# Power_PMIC.net
KiCad netlist of a schematic drawn in Altium Designer
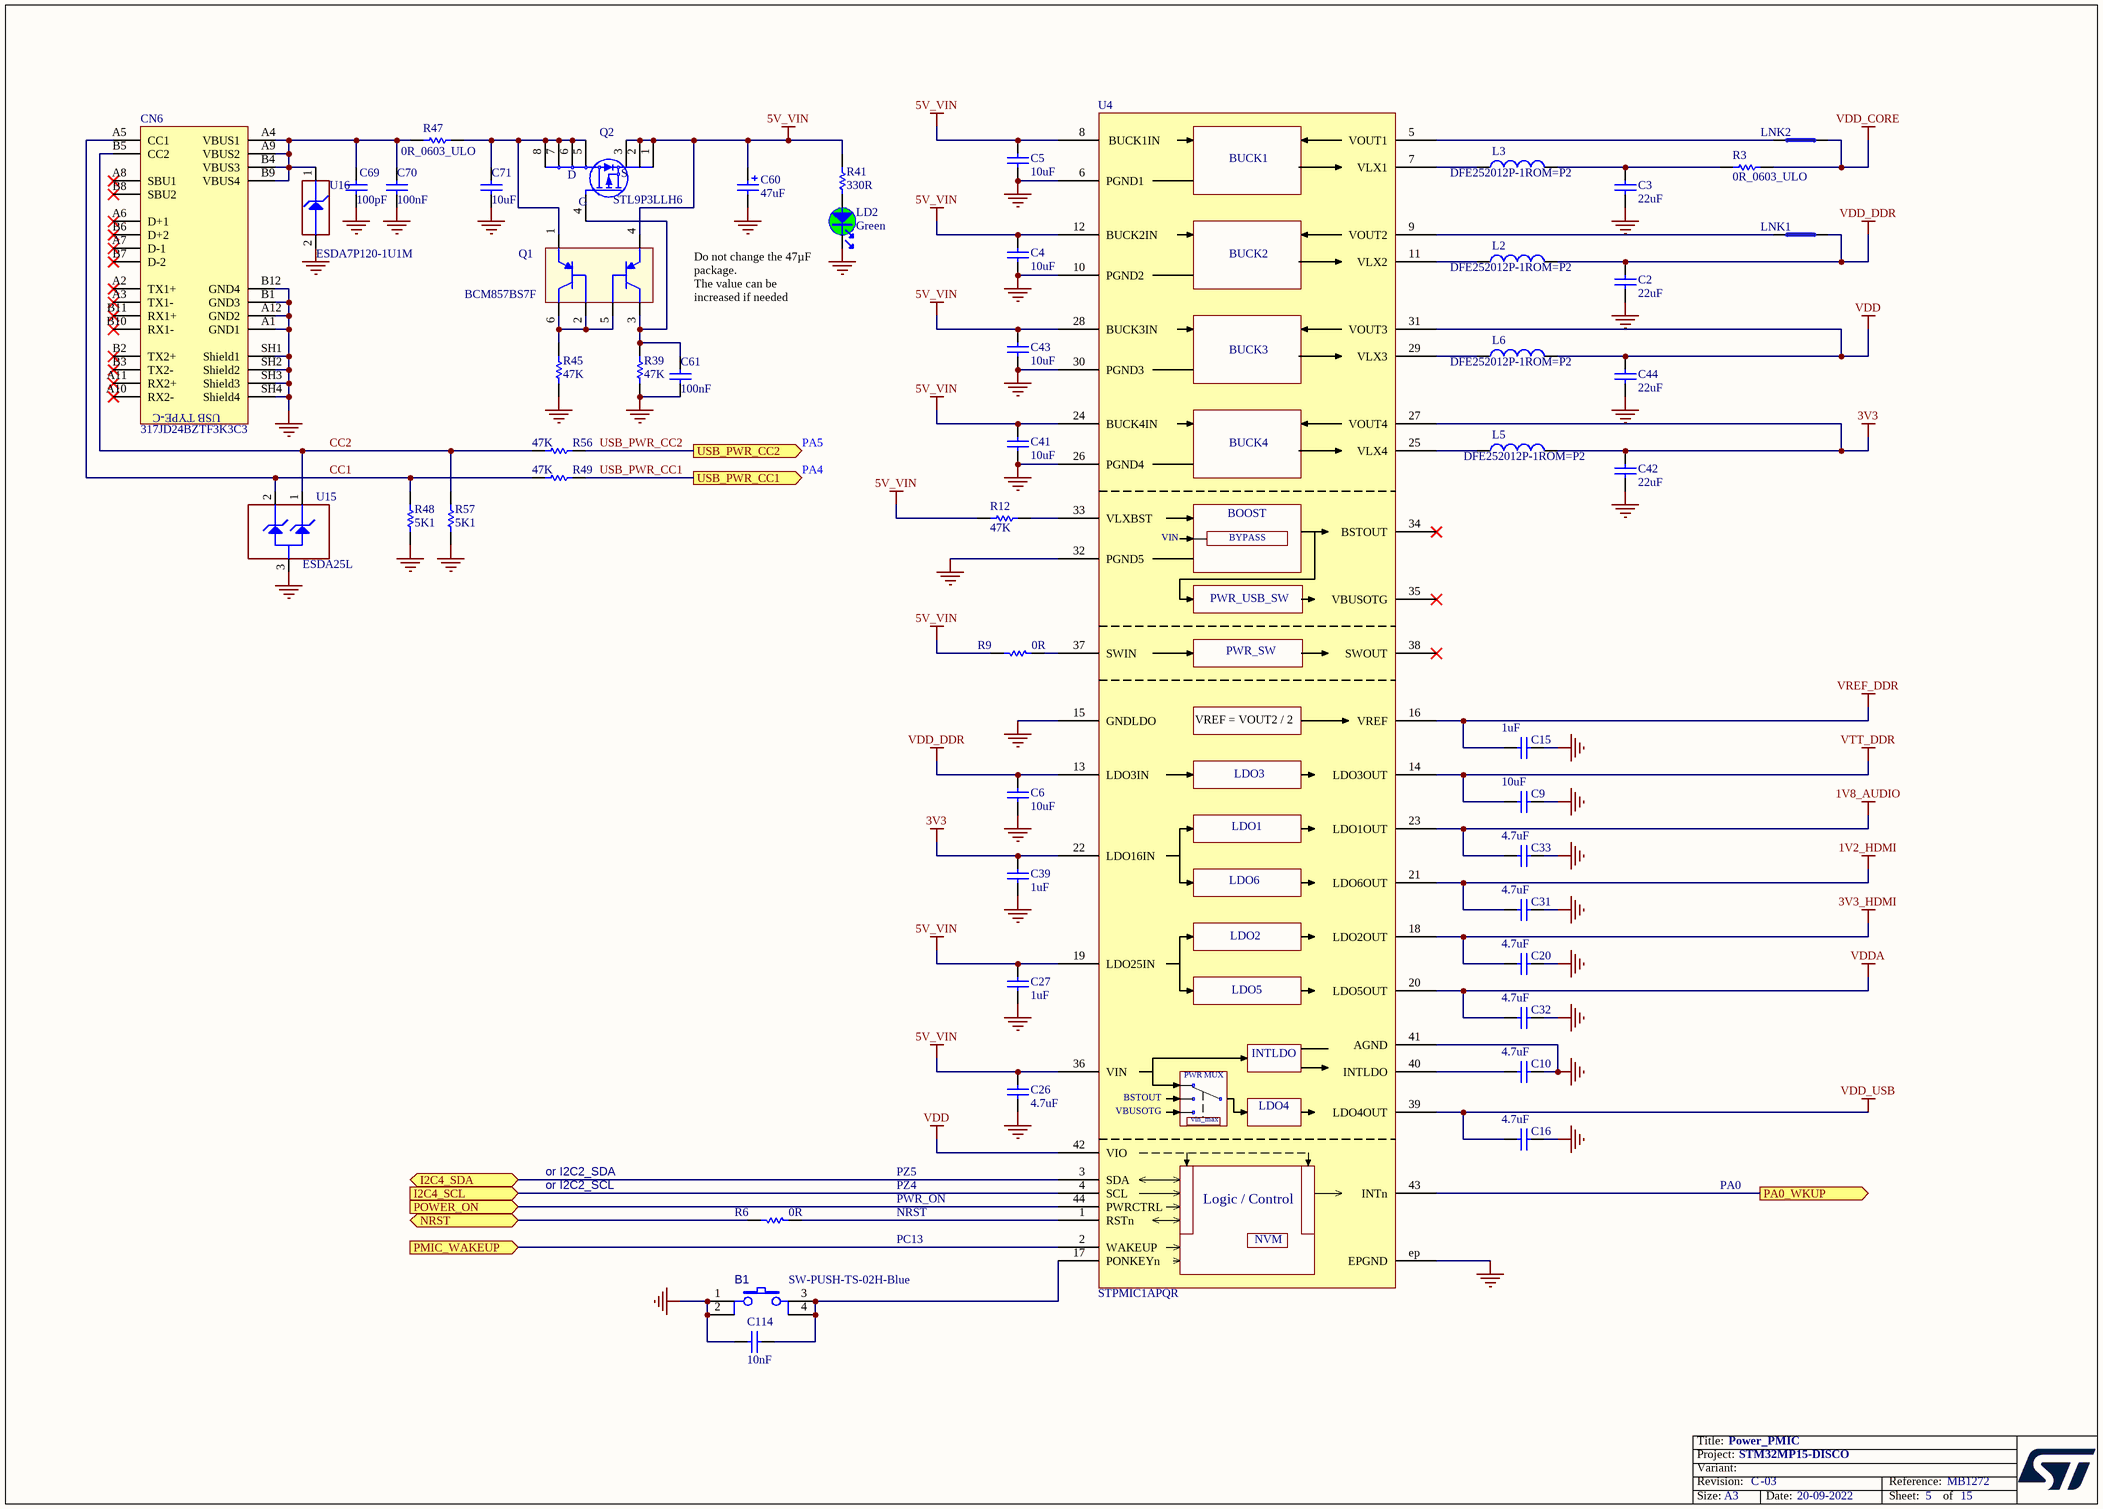
[diagram p0: Power_PMIC.SchDoc]

(export (version "E")
  (design (tool "Eeschema 10.0.6"))
  (components
    (comp (ref "B1")
      (value "SW-PUSH-TS-02H-Blue")
      (footprint "SWI_JIUBABA_C-TS-02H-2-5-B-V-T_R_BLUE")
      (description "Switch HW SMD blue")
      (fields
        (field (name "INTERNAL_PART_NUMBER") "MCD-00172")
        (field (name "MANUFACTURER_PART_NUMBER") "C-TS-02H-2.5-B-V-T/R BLUE")
        (field (name "PROVIDED_BY") "SUBCO")
      )
      (libsource (lib "MCD_PARTS_database") (part "SW-PUSH-TS-02H-Blue"))
    )
    (comp (ref "C2")
      (value "22uF")
      (footprint "C0603")
      (description "Capacitor, MLCC, 22uF, 6V3, X5R, 20%, 0603, T=0,8mm")
      (fields
        (field (name "INTERNAL_PART_NUMBER") "MCD-00100")
        (field (name "MANUFACTURER_PART_NUMBER") "GRM188R60J226MEA0J")
        (field (name "PROVIDED_BY") "SUBCO")
      )
      (libsource (lib "MCD_PARTS_database") (part "Capacitor"))
    )
    (comp (ref "C3")
      (value "22uF")
      (footprint "C0603")
      (description "Capacitor, MLCC, 22uF, 6V3, X5R, 20%, 0603, T=0,8mm")
      (fields
        (field (name "INTERNAL_PART_NUMBER") "MCD-00100")
        (field (name "MANUFACTURER_PART_NUMBER") "GRM188R60J226MEA0J")
        (field (name "PROVIDED_BY") "SUBCO")
      )
      (libsource (lib "MCD_PARTS_database") (part "Capacitor"))
    )
    (comp (ref "C4")
      (value "10uF")
      (footprint "C0603")
      (description "Capacitor, MLCC, 10uF, 10V, X5R, 10%, 0603, T=0,8mm")
      (fields
        (field (name "INTERNAL_PART_NUMBER") "MCD-00099")
        (field (name "MANUFACTURER_PART_NUMBER") "GRM188R61A106KE69D")
        (field (name "PROVIDED_BY") "SUBCO")
      )
      (libsource (lib "MCD_PARTS_database") (part "Capacitor"))
    )
    (comp (ref "C5")
      (value "10uF")
      (footprint "C0603")
      (description "Capacitor, MLCC, 10uF, 10V, X5R, 10%, 0603, T=0,8mm")
      (fields
        (field (name "INTERNAL_PART_NUMBER") "MCD-00099")
        (field (name "MANUFACTURER_PART_NUMBER") "GRM188R61A106KE69D")
        (field (name "PROVIDED_BY") "SUBCO")
      )
      (libsource (lib "MCD_PARTS_database") (part "Capacitor"))
    )
    (comp (ref "C6")
      (value "10uF")
      (footprint "C0603")
      (description "Capacitor, MLCC, 10uF, 10V, X5R, 10%, 0603, T=0,8mm")
      (fields
        (field (name "INTERNAL_PART_NUMBER") "MCD-00099")
        (field (name "MANUFACTURER_PART_NUMBER") "GRM188R61A106KE69D")
        (field (name "PROVIDED_BY") "SUBCO")
      )
      (libsource (lib "MCD_PARTS_database") (part "Capacitor"))
    )
    (comp (ref "C9")
      (value "10uF")
      (footprint "C0603")
      (description "Capacitor, MLCC, 10uF, 10V, X5R, 10%, 0603, T=0,8mm")
      (fields
        (field (name "INTERNAL_PART_NUMBER") "MCD-00099")
        (field (name "MANUFACTURER_PART_NUMBER") "GRM188R61A106KE69D")
        (field (name "PROVIDED_BY") "SUBCO")
      )
      (libsource (lib "MCD_PARTS_database") (part "Capacitor"))
    )
    (comp (ref "C10")
      (value "4.7uF")
      (footprint "C0402")
      (description "Capacitor, MLCC, 4.7uF, 6V3, X5R, 20%, 0402, T=0,5mm")
      (fields
        (field (name "INTERNAL_PART_NUMBER") "MCD-01356")
        (field (name "MANUFACTURER_PART_NUMBER") "GRM155R60J475ME47")
        (field (name "PROVIDED_BY") "SUBCO")
      )
      (libsource (lib "MCD_PARTS_database") (part "Capacitor"))
    )
    (comp (ref "C15")
      (value "1uF")
      (footprint "C0402")
      (description "Capacitor, MLCC, 1uF, 6V3, X5R, 10%, 0402, T=0,5mm")
      (fields
        (field (name "INTERNAL_PART_NUMBER") "MCD-00095")
        (field (name "MANUFACTURER_PART_NUMBER") "GRM155R61E105KA12")
        (field (name "PROVIDED_BY") "SUBCO")
      )
      (libsource (lib "MCD_PARTS_database") (part "Capacitor"))
    )
    (comp (ref "C16")
      (value "4.7uF")
      (footprint "C0402")
      (description "Capacitor, MLCC, 4.7uF, 6V3, X5R, 20%, 0402, T=0,5mm")
      (fields
        (field (name "INTERNAL_PART_NUMBER") "MCD-01356")
        (field (name "MANUFACTURER_PART_NUMBER") "GRM155R60J475ME47")
        (field (name "PROVIDED_BY") "SUBCO")
      )
      (libsource (lib "MCD_PARTS_database") (part "Capacitor"))
    )
    (comp (ref "C20")
      (value "4.7uF")
      (footprint "C0402")
      (description "Capacitor, MLCC, 4.7uF, 6V3, X5R, 20%, 0402, T=0,5mm")
      (fields
        (field (name "INTERNAL_PART_NUMBER") "MCD-01356")
        (field (name "MANUFACTURER_PART_NUMBER") "GRM155R60J475ME47")
        (field (name "PROVIDED_BY") "SUBCO")
      )
      (libsource (lib "MCD_PARTS_database") (part "Capacitor"))
    )
    (comp (ref "C26")
      (value "4.7uF")
      (footprint "C0402")
      (description "Capacitor, MLCC, 4.7uF, 6V3, X5R, 20%, 0402, T=0,5mm")
      (fields
        (field (name "INTERNAL_PART_NUMBER") "MCD-01356")
        (field (name "MANUFACTURER_PART_NUMBER") "GRM155R60J475ME47")
        (field (name "PROVIDED_BY") "SUBCO")
      )
      (libsource (lib "MCD_PARTS_database") (part "Capacitor"))
    )
    (comp (ref "C27")
      (value "1uF")
      (footprint "C0402")
      (description "Capacitor, MLCC, 1uF, 6V3, X5R, 10%, 0402, T=0,5mm")
      (fields
        (field (name "INTERNAL_PART_NUMBER") "MCD-00095")
        (field (name "MANUFACTURER_PART_NUMBER") "GRM155R61E105KA12")
        (field (name "PROVIDED_BY") "SUBCO")
      )
      (libsource (lib "MCD_PARTS_database") (part "Capacitor"))
    )
    (comp (ref "C31")
      (value "4.7uF")
      (footprint "C0402")
      (description "Capacitor, MLCC, 4.7uF, 6V3, X5R, 20%, 0402, T=0,5mm")
      (fields
        (field (name "INTERNAL_PART_NUMBER") "MCD-01356")
        (field (name "MANUFACTURER_PART_NUMBER") "GRM155R60J475ME47")
        (field (name "PROVIDED_BY") "SUBCO")
      )
      (libsource (lib "MCD_PARTS_database") (part "Capacitor"))
    )
    (comp (ref "C32")
      (value "4.7uF")
      (footprint "C0402")
      (description "Capacitor, MLCC, 4.7uF, 6V3, X5R, 20%, 0402, T=0,5mm")
      (fields
        (field (name "INTERNAL_PART_NUMBER") "MCD-01356")
        (field (name "MANUFACTURER_PART_NUMBER") "GRM155R60J475ME47")
        (field (name "PROVIDED_BY") "SUBCO")
      )
      (libsource (lib "MCD_PARTS_database") (part "Capacitor"))
    )
    (comp (ref "C33")
      (value "4.7uF")
      (footprint "C0402")
      (description "Capacitor, MLCC, 4.7uF, 6V3, X5R, 20%, 0402, T=0,5mm")
      (fields
        (field (name "INTERNAL_PART_NUMBER") "MCD-01356")
        (field (name "MANUFACTURER_PART_NUMBER") "GRM155R60J475ME47")
        (field (name "PROVIDED_BY") "SUBCO")
      )
      (libsource (lib "MCD_PARTS_database") (part "Capacitor"))
    )
    (comp (ref "C39")
      (value "1uF")
      (footprint "C0402")
      (description "Capacitor, MLCC, 1uF, 6V3, X5R, 10%, 0402, T=0,5mm")
      (fields
        (field (name "INTERNAL_PART_NUMBER") "MCD-00095")
        (field (name "MANUFACTURER_PART_NUMBER") "GRM155R61E105KA12")
        (field (name "PROVIDED_BY") "SUBCO")
      )
      (libsource (lib "MCD_PARTS_database") (part "Capacitor"))
    )
    (comp (ref "C41")
      (value "10uF")
      (footprint "C0603")
      (description "Capacitor, MLCC, 10uF, 10V, X5R, 10%, 0603, T=0,8mm")
      (fields
        (field (name "INTERNAL_PART_NUMBER") "MCD-00099")
        (field (name "MANUFACTURER_PART_NUMBER") "GRM188R61A106KE69D")
        (field (name "PROVIDED_BY") "SUBCO")
      )
      (libsource (lib "MCD_PARTS_database") (part "Capacitor"))
    )
    (comp (ref "C42")
      (value "22uF")
      (footprint "C0603")
      (description "Capacitor, MLCC, 22uF, 6V3, X5R, 20%, 0603, T=0,8mm")
      (fields
        (field (name "INTERNAL_PART_NUMBER") "MCD-00100")
        (field (name "MANUFACTURER_PART_NUMBER") "GRM188R60J226MEA0J")
        (field (name "PROVIDED_BY") "SUBCO")
      )
      (libsource (lib "MCD_PARTS_database") (part "Capacitor"))
    )
    (comp (ref "C43")
      (value "10uF")
      (footprint "C0603")
      (description "Capacitor, MLCC, 10uF, 10V, X5R, 10%, 0603, T=0,8mm")
      (fields
        (field (name "INTERNAL_PART_NUMBER") "MCD-00099")
        (field (name "MANUFACTURER_PART_NUMBER") "GRM188R61A106KE69D")
        (field (name "PROVIDED_BY") "SUBCO")
      )
      (libsource (lib "MCD_PARTS_database") (part "Capacitor"))
    )
    (comp (ref "C44")
      (value "22uF")
      (footprint "C0603")
      (description "Capacitor, MLCC, 22uF, 6V3, X5R, 20%, 0603, T=0,8mm")
      (fields
        (field (name "INTERNAL_PART_NUMBER") "MCD-00100")
        (field (name "MANUFACTURER_PART_NUMBER") "GRM188R60J226MEA0J")
        (field (name "PROVIDED_BY") "SUBCO")
      )
      (libsource (lib "MCD_PARTS_database") (part "Capacitor"))
    )
    (comp (ref "C60")
      (value "47uF")
      (footprint "CPOL_TAJ-C_2312_H2P6")
      (description "Capacitor, Tantalum, 47uF, 16V, 10%, TypeC")
      (fields
        (field (name "INTERNAL_PART_NUMBER") "MCD-00559")
        (field (name "MANUFACTURER_PART_NUMBER") "TAJC476K016RNJ")
        (field (name "PROVIDED_BY") "SUBCO")
      )
      (libsource (lib "MCD_PARTS_database") (part "Cap_POL_TANA"))
    )
    (comp (ref "C61")
      (value "100nF")
      (footprint "C0402")
      (description "Capacitor,100nF,16V,X7R,10%,0402")
      (fields
        (field (name "INTERNAL_PART_NUMBER") "MCD-00006")
        (field (name "MANUFACTURER_PART_NUMBER") "CC0402KRX7R7BB104")
        (field (name "PROVIDED_BY") "SUBCO")
      )
      (libsource (lib "MCD_PARTS_database") (part "Capacitor"))
    )
    (comp (ref "C69")
      (value "100pF")
      (footprint "C0402")
      (description "Capacitor, MLCC, 100pF, 50V, NPO, 5%, 0402, T=0,5mm")
      (fields
        (field (name "INTERNAL_PART_NUMBER") "MCD-00205")
        (field (name "MANUFACTURER_PART_NUMBER") "CC0402JRNPO9BN101")
        (field (name "PROVIDED_BY") "SUBCO")
      )
      (libsource (lib "MCD_PARTS_database") (part "Capacitor"))
    )
    (comp (ref "C70")
      (value "100nF")
      (footprint "C0402")
      (description "Capacitor,100nF,16V,X7R,10%,0402")
      (fields
        (field (name "INTERNAL_PART_NUMBER") "MCD-00006")
        (field (name "MANUFACTURER_PART_NUMBER") "CC0402KRX7R7BB104")
        (field (name "PROVIDED_BY") "SUBCO")
      )
      (libsource (lib "MCD_PARTS_database") (part "Capacitor"))
    )
    (comp (ref "C71")
      (value "10uF")
      (footprint "C0805")
      (description "Capacitor, MLCC, 10uF, 25V, X5R, 10%, 0805, T=0,85mm")
      (fields
        (field (name "INTERNAL_PART_NUMBER") "MCD-00014")
        (field (name "MANUFACTURER_PART_NUMBER") "CC0805KRX5R8BB106")
        (field (name "PROVIDED_BY") "SUBCO")
      )
      (libsource (lib "MCD_PARTS_database") (part "Capacitor"))
    )
    (comp (ref "C114")
      (value "10nF")
      (footprint "C0402")
      (description "Capacitor, MLCC, 10nF, 16V, X7R, 10%, 0402, T=0.5mm")
      (fields
        (field (name "INTERNAL_PART_NUMBER") "MCD-00011")
        (field (name "MANUFACTURER_PART_NUMBER") "CC0402KRX7R7BB103")
        (field (name "PROVIDED_BY") "SUBCO")
      )
      (libsource (lib "MCD_PARTS_database") (part "Capacitor"))
    )
    (comp (ref "CN6")
      (value "317JD24BZTF3K3C3")
      (footprint "CON_USB-TYPEC_COXOC_317JD24BZTF3K3C3")
      (description "USB tyce C certified receptacle for 1.6mm pcb height")
      (fields
        (field (name "INTERNAL_PART_NUMBER") "MCD-01108")
        (field (name "MANUFACTURER") "CHANT SINCERE (COXOC)")
        (field (name "PROVIDED_BY") "SUBCO")
      )
      (libsource (lib "MCD_PARTS_database") (part "USB_TYPE_C_Receptacle_317JD24BZTF3K3C3"))
    )
    (comp (ref "L2")
      (value "IND_1uH_42mohm_3.2A")
      (footprint "IND_2520_TOKO_DFE252012P")
      (description "Power Inductor ,1µH,4.3A max,+-20%,0.042ohm,2520")
      (fields
        (field (name "INTERNAL_PART_NUMBER") "MCD-01122")
        (field (name "MANUFACTURER_PART_NUMBER") "DFE252012P-1ROM=P2")
        (field (name "MANUFACTURER") "MURATA")
        (field (name "PROVIDED_BY") "SUBCO")
      )
      (libsource (lib "MCD_PARTS_database") (part "IND_1uH_42mohm_3.2A"))
    )
    (comp (ref "L3")
      (value "IND_1uH_42mohm_3.2A")
      (footprint "IND_2520_TOKO_DFE252012P")
      (description "Power Inductor ,1µH,4.3A max,+-20%,0.042ohm,2520")
      (fields
        (field (name "INTERNAL_PART_NUMBER") "MCD-01122")
        (field (name "MANUFACTURER_PART_NUMBER") "DFE252012P-1ROM=P2")
        (field (name "MANUFACTURER") "MURATA")
        (field (name "PROVIDED_BY") "SUBCO")
      )
      (libsource (lib "MCD_PARTS_database") (part "IND_1uH_42mohm_3.2A"))
    )
    (comp (ref "L5")
      (value "IND_1uH_42mohm_3.2A")
      (footprint "IND_2520_TOKO_DFE252012P")
      (description "Power Inductor ,1µH,4.3A max,+-20%,0.042ohm,2520")
      (fields
        (field (name "INTERNAL_PART_NUMBER") "MCD-01122")
        (field (name "MANUFACTURER_PART_NUMBER") "DFE252012P-1ROM=P2")
        (field (name "MANUFACTURER") "MURATA")
        (field (name "PROVIDED_BY") "SUBCO")
      )
      (libsource (lib "MCD_PARTS_database") (part "IND_1uH_42mohm_3.2A"))
    )
    (comp (ref "L6")
      (value "IND_1uH_42mohm_3.2A")
      (footprint "IND_2520_TOKO_DFE252012P")
      (description "Power Inductor ,1µH,4.3A max,+-20%,0.042ohm,2520")
      (fields
        (field (name "INTERNAL_PART_NUMBER") "MCD-01122")
        (field (name "MANUFACTURER_PART_NUMBER") "DFE252012P-1ROM=P2")
        (field (name "MANUFACTURER") "MURATA")
        (field (name "PROVIDED_BY") "SUBCO")
      )
      (libsource (lib "MCD_PARTS_database") (part "IND_1uH_42mohm_3.2A"))
    )
    (comp (ref "LD2")
      (value "Green")
      (footprint "LED_0603_GREEN")
      (description "LED, Green, 2V, 20mA, 0603")
      (fields (field (name "INTERNAL_PART_NUMBER") "MCD-02900") (field (name "MANUFACTURER") "EVERLIGHT"))
      (libsource (lib "MCD_PARTS_database") (part "LED_green"))
    )
    (comp (ref "LNK1")
      (value "link_200")
      (footprint "LINK200")
      (description "link 0.2mm")
      (libsource (lib "MCD_Temp_LBE") (part "link_200"))
    )
    (comp (ref "LNK2")
      (value "link_200")
      (footprint "LINK200")
      (description "link 0.2mm")
      (libsource (lib "MCD_Temp_LBE") (part "link_200"))
    )
    (comp (ref "Q1")
      (value "BCM857BS7F")
      (footprint "DIO_SOT363")
      (description "Transistor 45V Matched Pair PNP small Signal transistor in SOT363")
      (fields
        (field (name "INTERNAL_PART_NUMBER") "MCD-01120")
        (field (name "MANUFACTURER") "DIODES_INC")
        (field (name "PROVIDED_BY") "SUBCO")
      )
      (libsource (lib "MCD_PARTS_database") (part "BCM857BS"))
    )
    (comp (ref "Q2")
      (value "STL9P3LLH6")
      (footprint "MOS_POWERFLAT_3P3X3P3_P065")
      (description "Power Mosfet, P-channel,VDS -30V,RDS 12mohm typ,ID -9A")
      (fields
        (field (name "INTERNAL_PART_NUMBER") "MCD-01126")
        (field (name "MANUFACTURER") "STMICROELECTRONICS")
        (field (name "PROVIDED_BY") "SUBCO with ST control")
      )
      (libsource (lib "MCD_PARTS_database") (part "STL9P3LLH6"))
    )
    (comp (ref "R3")
      (value "0R_0603_ULO")
      (footprint "R0603")
      (description "Resistor,0R,0603,ULO")
      (fields
        (field (name "INTERNAL_PART_NUMBER") "MCD-00181")
        (field (name "MANUFACTURER_PART_NUMBER") "PMR03EZPJ000")
        (field (name "PROVIDED_BY") "SUBCO")
      )
      (libsource (lib "MCD_PARTS_database") (part "Resistor"))
    )
    (comp (ref "R6")
      (value "0R")
      (footprint "R0402")
      (description "Resistor,0R,0402,5%,1/16W")
      (fields
        (field (name "INTERNAL_PART_NUMBER") "MCD-00052")
        (field (name "MANUFACTURER_PART_NUMBER") "RC0402JR-070RL")
        (field (name "PROVIDED_BY") "SUBCO")
      )
      (libsource (lib "MCD_PARTS_database") (part "Resistor"))
    )
    (comp (ref "R9")
      (value "0R")
      (footprint "R0402")
      (description "Resistor,0R,0402,5%,1/16W")
      (fields
        (field (name "INTERNAL_PART_NUMBER") "MCD-00052")
        (field (name "MANUFACTURER_PART_NUMBER") "RC0402JR-070RL")
        (field (name "PROVIDED_BY") "SUBCO")
      )
      (libsource (lib "MCD_PARTS_database") (part "Resistor"))
    )
    (comp (ref "R12")
      (value "47K")
      (footprint "R0402")
      (description "Resistor,47K,0402,1%,1/16W")
      (fields
        (field (name "INTERNAL_PART_NUMBER") "MCD-00063")
        (field (name "MANUFACTURER_PART_NUMBER") "RC0402FR-0747KL")
        (field (name "PROVIDED_BY") "SUBCO")
      )
      (libsource (lib "MCD_PARTS_database") (part "Resistor"))
    )
    (comp (ref "R39")
      (value "47K")
      (footprint "R0402")
      (description "Resistor,47K,0402,1%,1/16W")
      (fields
        (field (name "INTERNAL_PART_NUMBER") "MCD-00063")
        (field (name "MANUFACTURER_PART_NUMBER") "RC0402FR-0747KL")
        (field (name "PROVIDED_BY") "SUBCO")
      )
      (libsource (lib "MCD_PARTS_database") (part "Resistor"))
    )
    (comp (ref "R41")
      (value "330R")
      (footprint "R0402")
      (description "Resistor,330R,0402,1%,1/16W")
      (fields
        (field (name "INTERNAL_PART_NUMBER") "MCD-00062")
        (field (name "MANUFACTURER_PART_NUMBER") "RC0402FR-07330RL")
        (field (name "PROVIDED_BY") "SUBCO")
      )
      (libsource (lib "MCD_PARTS_database") (part "Resistor"))
    )
    (comp (ref "R45")
      (value "47K")
      (footprint "R0402")
      (description "Resistor,47K,0402,1%,1/16W")
      (fields
        (field (name "INTERNAL_PART_NUMBER") "MCD-00063")
        (field (name "MANUFACTURER_PART_NUMBER") "RC0402FR-0747KL")
        (field (name "PROVIDED_BY") "SUBCO")
      )
      (libsource (lib "MCD_PARTS_database") (part "Resistor"))
    )
    (comp (ref "R47")
      (value "0R_0603_ULO")
      (footprint "R0603")
      (description "Resistor,0R,0603,ULO")
      (fields
        (field (name "INTERNAL_PART_NUMBER") "MCD-00181")
        (field (name "MANUFACTURER_PART_NUMBER") "PMR03EZPJ000")
        (field (name "PROVIDED_BY") "SUBCO")
      )
      (libsource (lib "MCD_PARTS_database") (part "Resistor"))
    )
    (comp (ref "R48")
      (value "5K1")
      (footprint "R0402")
      (description "Resistor,5K1,0402,1%,1/16W")
      (fields
        (field (name "INTERNAL_PART_NUMBER") "MCD-00333")
        (field (name "MANUFACTURER_PART_NUMBER") "RC0402FR-075K1L")
        (field (name "PROVIDED_BY") "SUBCO")
      )
      (libsource (lib "MCD_PARTS_database") (part "Resistor"))
    )
    (comp (ref "R49")
      (value "47K")
      (footprint "R0402")
      (description "Resistor,47K,0402,1%,1/16W")
      (fields
        (field (name "INTERNAL_PART_NUMBER") "MCD-00063")
        (field (name "MANUFACTURER_PART_NUMBER") "RC0402FR-0747KL")
        (field (name "PROVIDED_BY") "SUBCO")
      )
      (libsource (lib "MCD_PARTS_database") (part "Resistor"))
    )
    (comp (ref "R56")
      (value "47K")
      (footprint "R0402")
      (description "Resistor,47K,0402,1%,1/16W")
      (fields
        (field (name "INTERNAL_PART_NUMBER") "MCD-00063")
        (field (name "MANUFACTURER_PART_NUMBER") "RC0402FR-0747KL")
        (field (name "PROVIDED_BY") "SUBCO")
      )
      (libsource (lib "MCD_PARTS_database") (part "Resistor"))
    )
    (comp (ref "R57")
      (value "5K1")
      (footprint "R0402")
      (description "Resistor,5K1,0402,1%,1/16W")
      (fields
        (field (name "INTERNAL_PART_NUMBER") "MCD-00333")
        (field (name "MANUFACTURER_PART_NUMBER") "RC0402FR-075K1L")
        (field (name "PROVIDED_BY") "SUBCO")
      )
      (libsource (lib "MCD_PARTS_database") (part "Resistor"))
    )
    (comp (ref "U4")
      (value "STPMIC1APQR")
      (footprint "ICC_WFQFN44-EPAD_5X6_P040")
      (fields
        (field (name "INTERNAL_PART_NUMBER") "MCD-01650")
        (field (name "MANUFACTURER") "STMICROELECTRONICS")
        (field (name "Comment") "STPMU1")
        (field (name "PROVIDED_BY") "SUBCO with ST control")
      )
      (libsource (lib "MCD_PARTS_database") (part "STPMU1"))
    )
    (comp (ref "U15")
      (value "ESDA25L")
      (footprint "ESD_SOT23")
      (description "DUAL TRANSIL ARRAY FOR ESD PROTECTION")
      (fields
        (field (name "INTERNAL_PART_NUMBER") "MCD-01125")
        (field (name "MANUFACTURER") "STMICROELECTRONICS")
        (field (name "PROVIDED_BY") "SUBCO with ST control")
      )
      (libsource (lib "MCD_PARTS_database") (part "ESDA25L"))
    )
    (comp (ref "U16")
      (value "ESDA7P120-1U1M")
      (footprint "ESD_QFN1610_2N_1K_2A")
      (description "High power transient voltage suppressor")
      (fields
        (field (name "INTERNAL_PART_NUMBER") "MCD-01026")
        (field (name "MANUFACTURER") "STMICROELECTRONICS")
        (field (name "PROVIDED_BY") "SUBCO with ST control")
      )
      (libsource (lib "MCD_PARTS_database") (part "ESD-TRANSIL"))
    )
  )
  (nets
    (net (code "1") (name "/CC1") (class "Default")
      (node (ref "CN6") (pin "A5") (pinfunction "CC1_A5") (pintype "passive"))
      (node (ref "R48") (pin "2") (pinfunction "2_2") (pintype "passive"))
      (node (ref "R49") (pin "1") (pinfunction "1_1") (pintype "passive"))
      (node (ref "U15") (pin "2") (pinfunction "IO2_2") (pintype "passive"))
    )
    (net (code "2") (name "/CC2") (class "Default")
      (node (ref "CN6") (pin "B5") (pinfunction "CC2_B5") (pintype "passive"))
      (node (ref "R56") (pin "1") (pinfunction "1_1") (pintype "passive"))
      (node (ref "R57") (pin "2") (pinfunction "2_2") (pintype "passive"))
      (node (ref "U15") (pin "1") (pinfunction "IO1_1") (pintype "passive"))
    )
    (net (code "3") (name "/I2C4_SCL") (class "Default")
      (node (ref "U4") (pin "4") (pinfunction "SCL_4") (pintype "passive"))
    )
    (net (code "4") (name "/I2C4_SDA") (class "Default")
      (node (ref "U4") (pin "3") (pinfunction "SDA_3") (pintype "passive"))
    )
    (net (code "5") (name "/NRST") (class "Default")
      (node (ref "R6") (pin "1") (pinfunction "1_1") (pintype "passive"))
    )
    (net (code "6") (name "/PA0_WKUP") (class "Default")
      (node (ref "U4") (pin "43") (pinfunction "INTn_43") (pintype "passive"))
    )
    (net (code "7") (name "/PMIC_WAKEUP") (class "Default")
      (node (ref "U4") (pin "2") (pinfunction "WAKEUP_2") (pintype "passive"))
    )
    (net (code "8") (name "/POWER_ON") (class "Default")
      (node (ref "U4") (pin "44") (pinfunction "PWRCTRL_44") (pintype "passive"))
    )
    (net (code "9") (name "/USB_PWR_CC1") (class "Default")
      (node (ref "R49") (pin "2") (pinfunction "2_2") (pintype "passive"))
    )
    (net (code "10") (name "/USB_PWR_CC2") (class "Default")
      (node (ref "R56") (pin "2") (pinfunction "2_2") (pintype "passive"))
    )
    (net (code "11") (name "1V2_HDMI") (class "Default")
      (node (ref "C31") (pin "2") (pinfunction "2_2") (pintype "passive"))
      (node (ref "U4") (pin "21") (pinfunction "LDO6OUT_21") (pintype "passive"))
    )
    (net (code "12") (name "1V8_AUDIO") (class "Default")
      (node (ref "C33") (pin "2") (pinfunction "2_2") (pintype "passive"))
      (node (ref "U4") (pin "23") (pinfunction "LDO1OUT_23") (pintype "passive"))
    )
    (net (code "13") (name "3V3") (class "Default")
      (node (ref "C39") (pin "2") (pinfunction "2_2") (pintype "passive"))
      (node (ref "C42") (pin "2") (pinfunction "2_2") (pintype "passive"))
      (node (ref "L5") (pin "2") (pinfunction "2_2") (pintype "passive"))
      (node (ref "U4") (pin "22") (pinfunction "LDO16IN_22") (pintype "passive"))
      (node (ref "U4") (pin "27") (pinfunction "VOUT4_27") (pintype "passive"))
    )
    (net (code "14") (name "3V3_HDMI") (class "Default")
      (node (ref "C20") (pin "2") (pinfunction "2_2") (pintype "passive"))
      (node (ref "U4") (pin "18") (pinfunction "LDO2OUT_18") (pintype "passive"))
    )
    (net (code "15") (name "5V_VIN") (class "Default")
      (node (ref "C26") (pin "2") (pinfunction "2_2") (pintype "passive"))
      (node (ref "C27") (pin "2") (pinfunction "2_2") (pintype "passive"))
      (node (ref "C4") (pin "2") (pinfunction "2_2") (pintype "passive"))
      (node (ref "C41") (pin "2") (pinfunction "2_2") (pintype "passive"))
      (node (ref "C43") (pin "2") (pinfunction "2_2") (pintype "passive"))
      (node (ref "C5") (pin "2") (pinfunction "2_2") (pintype "passive"))
      (node (ref "C60") (pin "1") (pinfunction "1_1") (pintype "passive"))
      (node (ref "Q1") (pin "4") (pinfunction "E2_4") (pintype "passive"))
      (node (ref "Q2") (pin "1") (pinfunction "S_1") (pintype "passive"))
      (node (ref "Q2") (pin "2") (pinfunction "S_2") (pintype "passive"))
      (node (ref "Q2") (pin "3") (pinfunction "S_3") (pintype "passive"))
      (node (ref "R12") (pin "2") (pinfunction "2_2") (pintype "passive"))
      (node (ref "R41") (pin "2") (pinfunction "2_2") (pintype "passive"))
      (node (ref "R9") (pin "1") (pinfunction "1_1") (pintype "passive"))
      (node (ref "U4") (pin "12") (pinfunction "BUCK2IN_12") (pintype "passive"))
      (node (ref "U4") (pin "19") (pinfunction "LDO25IN_19") (pintype "passive"))
      (node (ref "U4") (pin "24") (pinfunction "BUCK4IN_24") (pintype "passive"))
      (node (ref "U4") (pin "28") (pinfunction "BUCK3IN_28") (pintype "passive"))
      (node (ref "U4") (pin "36") (pinfunction "VIN_36") (pintype "passive"))
      (node (ref "U4") (pin "8") (pinfunction "BUCK1IN_8") (pintype "passive"))
    )
    (net (code "16") (name "GND") (class "Default")
      (node (ref "B1") (pin "1") (pinfunction "1_1") (pintype "passive"))
      (node (ref "B1") (pin "2") (pinfunction "2_2") (pintype "passive"))
      (node (ref "C10") (pin "2") (pinfunction "2_2") (pintype "passive"))
      (node (ref "C114") (pin "1") (pinfunction "1_1") (pintype "passive"))
      (node (ref "C15") (pin "1") (pinfunction "1_1") (pintype "passive"))
      (node (ref "C16") (pin "1") (pinfunction "1_1") (pintype "passive"))
      (node (ref "C2") (pin "1") (pinfunction "1_1") (pintype "passive"))
      (node (ref "C20") (pin "1") (pinfunction "1_1") (pintype "passive"))
      (node (ref "C26") (pin "1") (pinfunction "1_1") (pintype "passive"))
      (node (ref "C27") (pin "1") (pinfunction "1_1") (pintype "passive"))
      (node (ref "C3") (pin "1") (pinfunction "1_1") (pintype "passive"))
      (node (ref "C31") (pin "1") (pinfunction "1_1") (pintype "passive"))
      (node (ref "C32") (pin "1") (pinfunction "1_1") (pintype "passive"))
      (node (ref "C33") (pin "1") (pinfunction "1_1") (pintype "passive"))
      (node (ref "C39") (pin "1") (pinfunction "1_1") (pintype "passive"))
      (node (ref "C4") (pin "1") (pinfunction "1_1") (pintype "passive"))
      (node (ref "C41") (pin "1") (pinfunction "1_1") (pintype "passive"))
      (node (ref "C42") (pin "1") (pinfunction "1_1") (pintype "passive"))
      (node (ref "C43") (pin "1") (pinfunction "1_1") (pintype "passive"))
      (node (ref "C44") (pin "1") (pinfunction "1_1") (pintype "passive"))
      (node (ref "C5") (pin "1") (pinfunction "1_1") (pintype "passive"))
      (node (ref "C6") (pin "1") (pinfunction "1_1") (pintype "passive"))
      (node (ref "C60") (pin "2") (pinfunction "2_2") (pintype "passive"))
      (node (ref "C61") (pin "2") (pinfunction "2_2") (pintype "passive"))
      (node (ref "C69") (pin "1") (pinfunction "1_1") (pintype "passive"))
      (node (ref "C70") (pin "2") (pinfunction "2_2") (pintype "passive"))
      (node (ref "C71") (pin "1") (pinfunction "1_1") (pintype "passive"))
      (node (ref "C9") (pin "1") (pinfunction "1_1") (pintype "passive"))
      (node (ref "CN6") (pin "A1") (pinfunction "GND1_A1") (pintype "passive"))
      (node (ref "CN6") (pin "A12") (pinfunction "GND2_A12") (pintype "passive"))
      (node (ref "CN6") (pin "B1") (pinfunction "GND3_B1") (pintype "passive"))
      (node (ref "CN6") (pin "B12") (pinfunction "GND4_B12") (pintype "passive"))
      (node (ref "CN6") (pin "SH1") (pinfunction "Shield1_SH1") (pintype "passive"))
      (node (ref "CN6") (pin "SH2") (pinfunction "Shield2_SH2") (pintype "passive"))
      (node (ref "CN6") (pin "SH3") (pinfunction "Shield3_SH3") (pintype "passive"))
      (node (ref "CN6") (pin "SH4") (pinfunction "Shield4_SH4") (pintype "passive"))
      (node (ref "LD2") (pin "2") (pintype "passive"))
      (node (ref "R39") (pin "1") (pinfunction "1_1") (pintype "passive"))
      (node (ref "R45") (pin "1") (pinfunction "1_1") (pintype "passive"))
      (node (ref "R48") (pin "1") (pinfunction "1_1") (pintype "passive"))
      (node (ref "R57") (pin "1") (pinfunction "1_1") (pintype "passive"))
      (node (ref "U15") (pin "3") (pinfunction "GND_3") (pintype "passive"))
      (node (ref "U16") (pin "2") (pinfunction "GND_2") (pintype "passive"))
      (node (ref "U4") (pin "10") (pinfunction "PGND2_10") (pintype "passive"))
      (node (ref "U4") (pin "15") (pinfunction "GNDLDO_15") (pintype "passive"))
      (node (ref "U4") (pin "26") (pinfunction "PGND4_26") (pintype "passive"))
      (node (ref "U4") (pin "30") (pinfunction "PGND3_30") (pintype "passive"))
      (node (ref "U4") (pin "32") (pinfunction "PGND5_32") (pintype "passive"))
      (node (ref "U4") (pin "41") (pinfunction "AGND_41") (pintype "passive"))
      (node (ref "U4") (pin "6") (pinfunction "PGND1_6") (pintype "passive"))
      (node (ref "U4") (pin "ep") (pinfunction "EPGND_ep") (pintype "passive"))
    )
    (net (code "17") (name "Net-(C3-Pad2)") (class "Default")
      (node (ref "C3") (pin "2") (pinfunction "2_2") (pintype "passive"))
      (node (ref "L3") (pin "2") (pinfunction "2_2") (pintype "passive"))
      (node (ref "R3") (pin "1") (pinfunction "1_1") (pintype "passive"))
    )
    (net (code "18") (name "Net-(CN6-VBUS1)") (class "Default")
      (node (ref "C69") (pin "2") (pinfunction "2_2") (pintype "passive"))
      (node (ref "C70") (pin "1") (pinfunction "1_1") (pintype "passive"))
      (node (ref "CN6") (pin "A4") (pinfunction "VBUS1_A4") (pintype "passive"))
      (node (ref "CN6") (pin "A9") (pinfunction "VBUS2_A9") (pintype "passive"))
      (node (ref "CN6") (pin "B4") (pinfunction "VBUS3_B4") (pintype "passive"))
      (node (ref "CN6") (pin "B9") (pinfunction "VBUS4_B9") (pintype "passive"))
      (node (ref "R47") (pin "1") (pinfunction "1_1") (pintype "passive"))
      (node (ref "U16") (pin "1") (pinfunction "IO1_1") (pintype "passive"))
    )
    (net (code "19") (name "Net-(LD2-Pad1)") (class "Default")
      (node (ref "LD2") (pin "1") (pintype "passive"))
      (node (ref "R41") (pin "1") (pinfunction "1_1") (pintype "passive"))
    )
    (net (code "20") (name "Net-(Q1-B1)") (class "Default")
      (node (ref "Q1") (pin "2") (pinfunction "B1_2") (pintype "passive"))
      (node (ref "Q1") (pin "5") (pinfunction "B2_5") (pintype "passive"))
      (node (ref "Q1") (pin "6") (pinfunction "C1_6") (pintype "passive"))
      (node (ref "R45") (pin "2") (pinfunction "2_2") (pintype "passive"))
    )
    (net (code "21") (name "Net-(Q1-C2)") (class "Default")
      (node (ref "C61") (pin "1") (pinfunction "1_1") (pintype "passive"))
      (node (ref "Q1") (pin "3") (pinfunction "C2_3") (pintype "passive"))
      (node (ref "Q2") (pin "4") (pinfunction "G_4") (pintype "passive"))
      (node (ref "R39") (pin "2") (pinfunction "2_2") (pintype "passive"))
    )
    (net (code "22") (name "Net-(Q1-E1)") (class "Default")
      (node (ref "C71") (pin "2") (pinfunction "2_2") (pintype "passive"))
      (node (ref "Q1") (pin "1") (pinfunction "E1_1") (pintype "passive"))
      (node (ref "Q2") (pin "5") (pinfunction "D_5") (pintype "passive"))
      (node (ref "Q2") (pin "6") (pinfunction "D_6") (pintype "passive"))
      (node (ref "Q2") (pin "7") (pinfunction "D_7") (pintype "passive"))
      (node (ref "Q2") (pin "8") (pinfunction "D_8") (pintype "passive"))
      (node (ref "R47") (pin "2") (pinfunction "2_2") (pintype "passive"))
    )
    (net (code "23") (name "Net-(U4-INTLDO)") (class "Default")
      (node (ref "C10") (pin "1") (pinfunction "1_1") (pintype "passive"))
      (node (ref "U4") (pin "40") (pinfunction "INTLDO_40") (pintype "passive"))
    )
    (net (code "24") (name "Net-(U4-PONKEYn)") (class "Default")
      (node (ref "B1") (pin "3") (pinfunction "3_3") (pintype "passive"))
      (node (ref "B1") (pin "4") (pinfunction "4_4") (pintype "passive"))
      (node (ref "C114") (pin "2") (pinfunction "2_2") (pintype "passive"))
      (node (ref "U4") (pin "17") (pinfunction "PONKEYn_17") (pintype "passive"))
    )
    (net (code "25") (name "Net-(U4-RSTn)") (class "Default")
      (node (ref "R6") (pin "2") (pinfunction "2_2") (pintype "passive"))
      (node (ref "U4") (pin "1") (pinfunction "RSTn_1") (pintype "passive"))
    )
    (net (code "26") (name "Net-(U4-SWIN)") (class "Default")
      (node (ref "R9") (pin "2") (pinfunction "2_2") (pintype "passive"))
      (node (ref "U4") (pin "37") (pinfunction "SWIN_37") (pintype "passive"))
    )
    (net (code "27") (name "Net-(U4-VLX1)") (class "Default")
      (node (ref "L3") (pin "1") (pinfunction "1_1") (pintype "passive"))
      (node (ref "U4") (pin "7") (pinfunction "VLX1_7") (pintype "passive"))
    )
    (net (code "28") (name "Net-(U4-VLX2)") (class "Default")
      (node (ref "L2") (pin "1") (pinfunction "1_1") (pintype "passive"))
      (node (ref "U4") (pin "11") (pinfunction "VLX2_11") (pintype "passive"))
    )
    (net (code "29") (name "Net-(U4-VLX3)") (class "Default")
      (node (ref "L6") (pin "1") (pinfunction "1_1") (pintype "passive"))
      (node (ref "U4") (pin "29") (pinfunction "VLX3_29") (pintype "passive"))
    )
    (net (code "30") (name "Net-(U4-VLX4)") (class "Default")
      (node (ref "L5") (pin "1") (pinfunction "1_1") (pintype "passive"))
      (node (ref "U4") (pin "25") (pinfunction "VLX4_25") (pintype "passive"))
    )
    (net (code "31") (name "Net-(U4-VLXBST)") (class "Default")
      (node (ref "R12") (pin "1") (pinfunction "1_1") (pintype "passive"))
      (node (ref "U4") (pin "33") (pinfunction "VLXBST_33") (pintype "passive"))
    )
    (net (code "32") (name "Net-(U4-VOUT1)") (class "Default")
      (node (ref "LNK2") (pin "1") (pinfunction "1_1") (pintype "passive"))
      (node (ref "U4") (pin "5") (pinfunction "VOUT1_5") (pintype "passive"))
    )
    (net (code "33") (name "Net-(U4-VOUT2)") (class "Default")
      (node (ref "LNK1") (pin "1") (pinfunction "1_1") (pintype "passive"))
      (node (ref "U4") (pin "9") (pinfunction "VOUT2_9") (pintype "passive"))
    )
    (net (code "34") (name "VDD") (class "Default")
      (node (ref "C44") (pin "2") (pinfunction "2_2") (pintype "passive"))
      (node (ref "L6") (pin "2") (pinfunction "2_2") (pintype "passive"))
      (node (ref "U4") (pin "31") (pinfunction "VOUT3_31") (pintype "passive"))
      (node (ref "U4") (pin "42") (pinfunction "VIO_42") (pintype "passive"))
    )
    (net (code "35") (name "VDDA") (class "Default")
      (node (ref "C32") (pin "2") (pinfunction "2_2") (pintype "passive"))
      (node (ref "U4") (pin "20") (pinfunction "LDO5OUT_20") (pintype "passive"))
    )
    (net (code "36") (name "VDD_CORE") (class "Default")
      (node (ref "LNK2") (pin "2") (pinfunction "2_2") (pintype "passive"))
      (node (ref "R3") (pin "2") (pinfunction "2_2") (pintype "passive"))
    )
    (net (code "37") (name "VDD_DDR") (class "Default")
      (node (ref "C2") (pin "2") (pinfunction "2_2") (pintype "passive"))
      (node (ref "C6") (pin "2") (pinfunction "2_2") (pintype "passive"))
      (node (ref "L2") (pin "2") (pinfunction "2_2") (pintype "passive"))
      (node (ref "LNK1") (pin "2") (pinfunction "2_2") (pintype "passive"))
      (node (ref "U4") (pin "13") (pinfunction "LDO3IN_13") (pintype "passive"))
    )
    (net (code "38") (name "VDD_USB") (class "Default")
      (node (ref "C16") (pin "2") (pinfunction "2_2") (pintype "passive"))
      (node (ref "U4") (pin "39") (pinfunction "LDO4OUT_39") (pintype "passive"))
    )
    (net (code "39") (name "VREF_DDR") (class "Default")
      (node (ref "C15") (pin "2") (pinfunction "2_2") (pintype "passive"))
      (node (ref "U4") (pin "16") (pinfunction "VREF_16") (pintype "passive"))
    )
    (net (code "40") (name "VTT_DDR") (class "Default")
      (node (ref "C9") (pin "2") (pinfunction "2_2") (pintype "passive"))
      (node (ref "U4") (pin "14") (pinfunction "LDO3OUT_14") (pintype "passive"))
    )
    (net (code "41") (name "unconnected-(CN6-D+1-PadA6)") (class "Default")
      (node (ref "CN6") (pin "A6") (pinfunction "D+1_A6") (pintype "passive+no_connect"))
    )
    (net (code "42") (name "unconnected-(CN6-D+2-PadB6)") (class "Default")
      (node (ref "CN6") (pin "B6") (pinfunction "D+2_B6") (pintype "passive+no_connect"))
    )
    (net (code "43") (name "unconnected-(CN6-D-1-PadA7)") (class "Default")
      (node (ref "CN6") (pin "A7") (pinfunction "D-1_A7") (pintype "passive+no_connect"))
    )
    (net (code "44") (name "unconnected-(CN6-D-2-PadB7)") (class "Default")
      (node (ref "CN6") (pin "B7") (pinfunction "D-2_B7") (pintype "passive+no_connect"))
    )
    (net (code "45") (name "unconnected-(CN6-RX1+-PadB11)") (class "Default")
      (node (ref "CN6") (pin "B11") (pinfunction "RX1+_B11") (pintype "passive+no_connect"))
    )
    (net (code "46") (name "unconnected-(CN6-RX1--PadB10)") (class "Default")
      (node (ref "CN6") (pin "B10") (pinfunction "RX1-_B10") (pintype "passive+no_connect"))
    )
    (net (code "47") (name "unconnected-(CN6-RX2+-PadA11)") (class "Default")
      (node (ref "CN6") (pin "A11") (pinfunction "RX2+_A11") (pintype "passive+no_connect"))
    )
    (net (code "48") (name "unconnected-(CN6-RX2--PadA10)") (class "Default")
      (node (ref "CN6") (pin "A10") (pinfunction "RX2-_A10") (pintype "passive+no_connect"))
    )
    (net (code "49") (name "unconnected-(CN6-SBU1-PadA8)") (class "Default")
      (node (ref "CN6") (pin "A8") (pinfunction "SBU1_A8") (pintype "passive+no_connect"))
    )
    (net (code "50") (name "unconnected-(CN6-SBU2-PadB8)") (class "Default")
      (node (ref "CN6") (pin "B8") (pinfunction "SBU2_B8") (pintype "passive+no_connect"))
    )
    (net (code "51") (name "unconnected-(CN6-TX1+-PadA2)") (class "Default")
      (node (ref "CN6") (pin "A2") (pinfunction "TX1+_A2") (pintype "passive+no_connect"))
    )
    (net (code "52") (name "unconnected-(CN6-TX1--PadA3)") (class "Default")
      (node (ref "CN6") (pin "A3") (pinfunction "TX1-_A3") (pintype "passive+no_connect"))
    )
    (net (code "53") (name "unconnected-(CN6-TX2+-PadB2)") (class "Default")
      (node (ref "CN6") (pin "B2") (pinfunction "TX2+_B2") (pintype "passive+no_connect"))
    )
    (net (code "54") (name "unconnected-(CN6-TX2--PadB3)") (class "Default")
      (node (ref "CN6") (pin "B3") (pinfunction "TX2-_B3") (pintype "passive+no_connect"))
    )
    (net (code "55") (name "unconnected-(U4-BSTOUT-Pad34)") (class "Default")
      (node (ref "U4") (pin "34") (pinfunction "BSTOUT_34") (pintype "passive+no_connect"))
    )
    (net (code "56") (name "unconnected-(U4-SWOUT-Pad38)") (class "Default")
      (node (ref "U4") (pin "38") (pinfunction "SWOUT_38") (pintype "passive+no_connect"))
    )
    (net (code "57") (name "unconnected-(U4-VBUSOTG-Pad35)") (class "Default")
      (node (ref "U4") (pin "35") (pinfunction "VBUSOTG_35") (pintype "passive+no_connect"))
    )
  )
)
